# Si_FET_Adapter.net
KiCad netlist of a schematic drawn in EAGLE
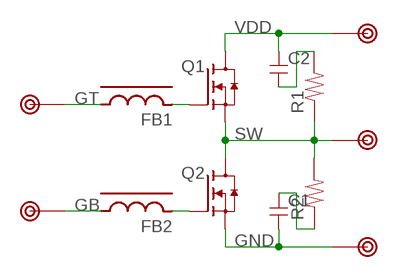
[diagram p0: schematic, sheet 1]

(export (version "E")
  (design (tool "Eeschema 10.0.6"))
  (components
    (comp (ref "C1")
      (value "C-3225-2")
      (footprint "eagle-import:3225-2")
      (libsource (lib "eagle-import") (part "C-3225-2"))
    )
    (comp (ref "C2")
      (value "C-3225-2")
      (footprint "eagle-import:3225-2")
      (libsource (lib "eagle-import") (part "C-3225-2"))
    )
    (comp (ref "FB1")
      (value "FB-1608FB")
      (footprint "eagle-import:1608-FB")
      (libsource (lib "eagle-import") (part "FB-1608FB"))
    )
    (comp (ref "FB2")
      (value "FB-1608FB")
      (footprint "eagle-import:1608-FB")
      (libsource (lib "eagle-import") (part "FB-1608FB"))
    )
    (comp (ref "Q1")
      (value "NMOS-DFN")
      (footprint "eagle-import:DFN5_5X6")
      (libsource (lib "eagle-import") (part "NMOS-DFN"))
    )
    (comp (ref "Q2")
      (value "NMOS-DFN")
      (footprint "eagle-import:DFN5_5X6")
      (libsource (lib "eagle-import") (part "NMOS-DFN"))
    )
    (comp (ref "R1")
      (value "R-2012-2")
      (footprint "eagle-import:2012-2")
      (libsource (lib "eagle-import") (part "R-2012-2"))
    )
    (comp (ref "R2")
      (value "R-2012-2")
      (footprint "eagle-import:2012-2")
      (libsource (lib "eagle-import") (part "R-2012-2"))
    )
    (comp (ref "TP1")
      (value "TESTPIN")
      (footprint "eagle-import:TESTPIN")
      (libsource (lib "eagle-import") (part "TESTPIN"))
    )
    (comp (ref "TP2")
      (value "TESTPIN-MID")
      (footprint "eagle-import:TESTPIN-MID")
      (libsource (lib "eagle-import") (part "TESTPIN-MID"))
    )
    (comp (ref "TP3")
      (value "TESTPIN-MID")
      (footprint "eagle-import:TESTPIN-MID")
      (libsource (lib "eagle-import") (part "TESTPIN-MID"))
    )
    (comp (ref "TP4")
      (value "TESTPIN-MID")
      (footprint "eagle-import:TESTPIN-MID")
      (libsource (lib "eagle-import") (part "TESTPIN-MID"))
    )
    (comp (ref "TP5")
      (value "TESTPIN-MID")
      (footprint "eagle-import:TESTPIN-MID")
      (libsource (lib "eagle-import") (part "TESTPIN-MID"))
    )
  )
  (nets
    (net (code "1") (name "/GB") (class "Default")
      (node (ref "FB2") (pin "1") (pinfunction "1_1") (pintype "passive"))
      (node (ref "TP4") (pin "1") (pinfunction "1_1") (pintype "passive"))
    )
    (net (code "2") (name "/GND") (class "Default")
      (node (ref "C1") (pin "2") (pinfunction "2_2") (pintype "passive"))
      (node (ref "Q2") (pin "1") (pinfunction "S_1") (pintype "passive"))
      (node (ref "Q2") (pin "2") (pinfunction "S_2") (pintype "passive"))
      (node (ref "Q2") (pin "3") (pinfunction "S_3") (pintype "passive"))
      (node (ref "TP3") (pin "1") (pinfunction "1_1") (pintype "passive"))
    )
    (net (code "3") (name "/GT") (class "Default")
      (node (ref "FB1") (pin "1") (pinfunction "1_1") (pintype "passive"))
      (node (ref "TP5") (pin "1") (pinfunction "1_1") (pintype "passive"))
    )
    (net (code "4") (name "/SW") (class "Default")
      (node (ref "Q1") (pin "1") (pinfunction "S_1") (pintype "passive"))
      (node (ref "Q1") (pin "2") (pinfunction "S_2") (pintype "passive"))
      (node (ref "Q1") (pin "3") (pinfunction "S_3") (pintype "passive"))
      (node (ref "Q2") (pin "5_6") (pinfunction "D_5_6") (pintype "passive"))
      (node (ref "Q2") (pin "5_6_1") (pinfunction "D_5_6_1") (pintype "passive"))
      (node (ref "Q2") (pin "5_6_2") (pinfunction "D_5_6_2") (pintype "passive"))
      (node (ref "Q2") (pin "5_6_3") (pinfunction "D_5_6_3") (pintype "passive"))
      (node (ref "Q2") (pin "5_6_4") (pinfunction "D_5_6_4") (pintype "passive"))
      (node (ref "R1") (pin "1") (pinfunction "1_1") (pintype "passive"))
      (node (ref "R2") (pin "2") (pinfunction "2_2") (pintype "passive"))
      (node (ref "TP2") (pin "1") (pinfunction "1_1") (pintype "passive"))
    )
    (net (code "5") (name "/VDD") (class "Default")
      (node (ref "C2") (pin "1") (pinfunction "1_1") (pintype "passive"))
      (node (ref "Q1") (pin "5_6") (pinfunction "D_5_6") (pintype "passive"))
      (node (ref "Q1") (pin "5_6_1") (pinfunction "D_5_6_1") (pintype "passive"))
      (node (ref "Q1") (pin "5_6_2") (pinfunction "D_5_6_2") (pintype "passive"))
      (node (ref "Q1") (pin "5_6_3") (pinfunction "D_5_6_3") (pintype "passive"))
      (node (ref "Q1") (pin "5_6_4") (pinfunction "D_5_6_4") (pintype "passive"))
      (node (ref "TP1") (pin "1") (pinfunction "1_1") (pintype "passive"))
    )
    (net (code "6") (name "Net-(C1-Pad1)") (class "Default")
      (node (ref "C1") (pin "1") (pinfunction "1_1") (pintype "passive"))
      (node (ref "R2") (pin "1") (pinfunction "1_1") (pintype "passive"))
    )
    (net (code "7") (name "Net-(C2-Pad2)") (class "Default")
      (node (ref "C2") (pin "2") (pinfunction "2_2") (pintype "passive"))
      (node (ref "R1") (pin "2") (pinfunction "2_2") (pintype "passive"))
    )
    (net (code "8") (name "Net-(Q1-G)") (class "Default")
      (node (ref "FB1") (pin "2") (pinfunction "2_2") (pintype "passive"))
      (node (ref "Q1") (pin "4") (pinfunction "G_4") (pintype "passive"))
    )
    (net (code "9") (name "Net-(Q2-G)") (class "Default")
      (node (ref "FB2") (pin "2") (pinfunction "2_2") (pintype "passive"))
      (node (ref "Q2") (pin "4") (pinfunction "G_4") (pintype "passive"))
    )
  )
)
